# POE.net
KiCad netlist of a schematic drawn in Altium Designer
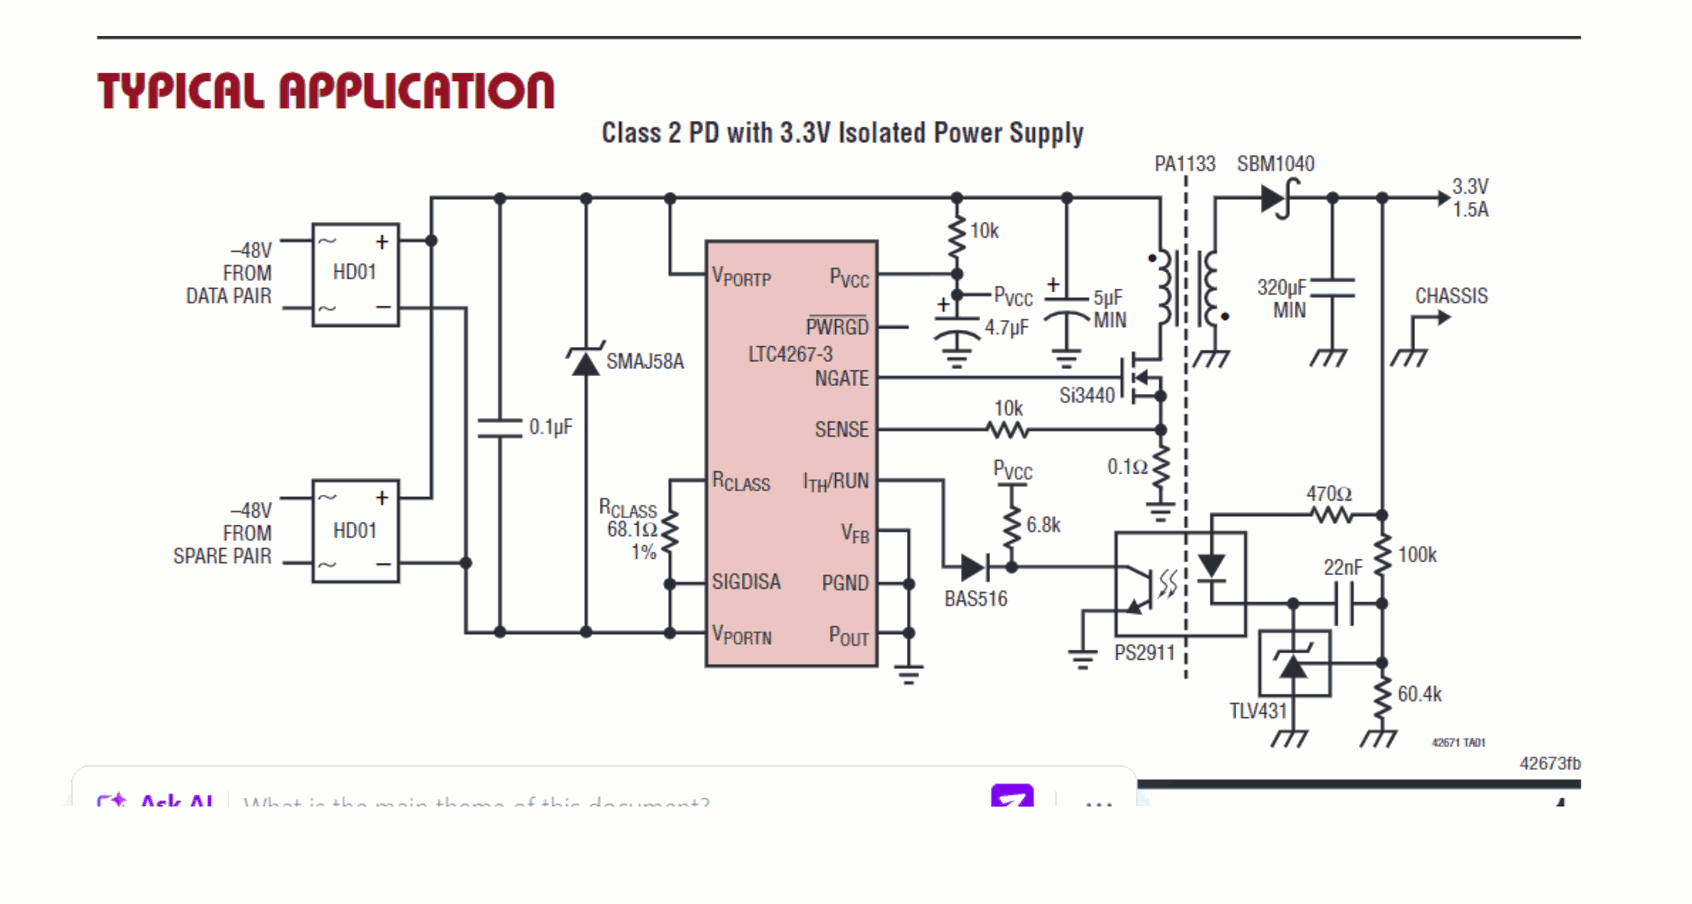
[diagram p0: POE.SchDoc, top left]
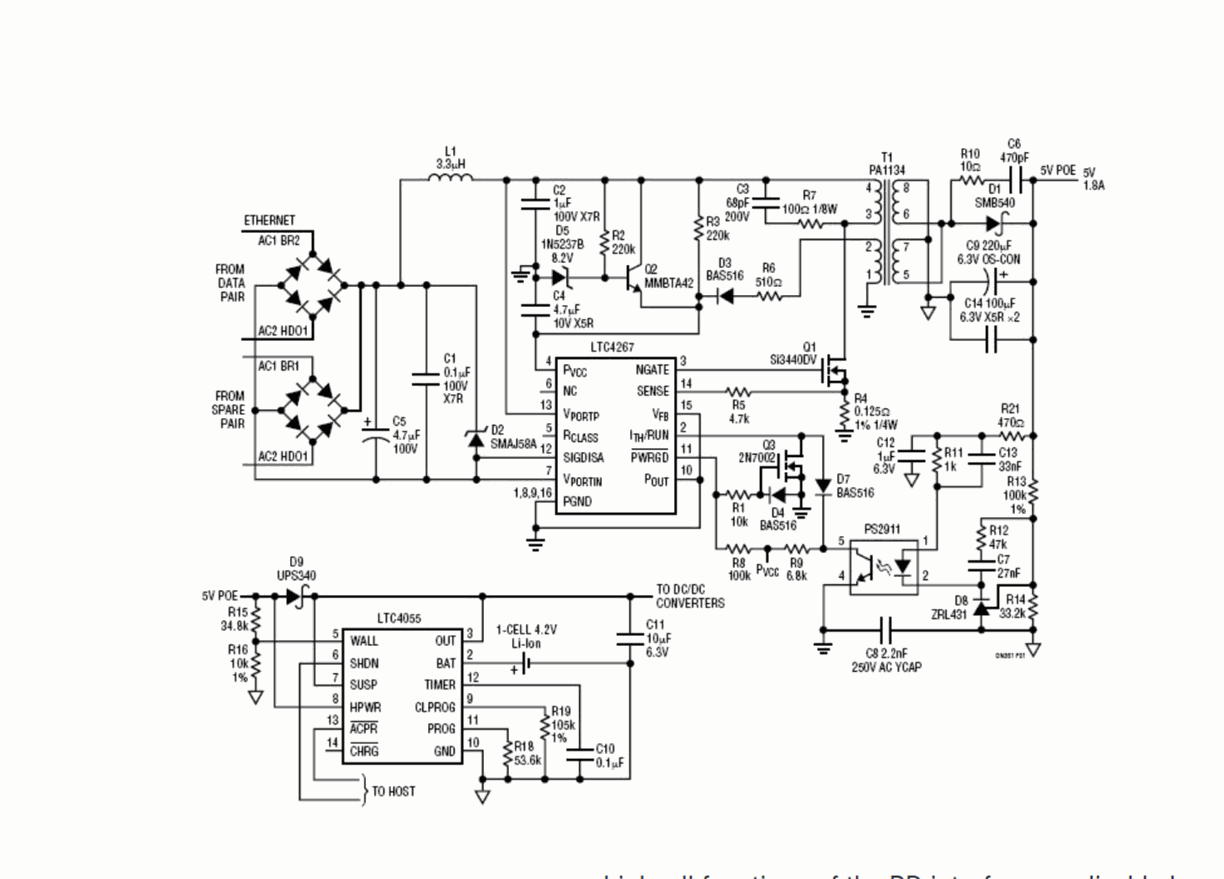
[diagram p1: POE.SchDoc, top right]
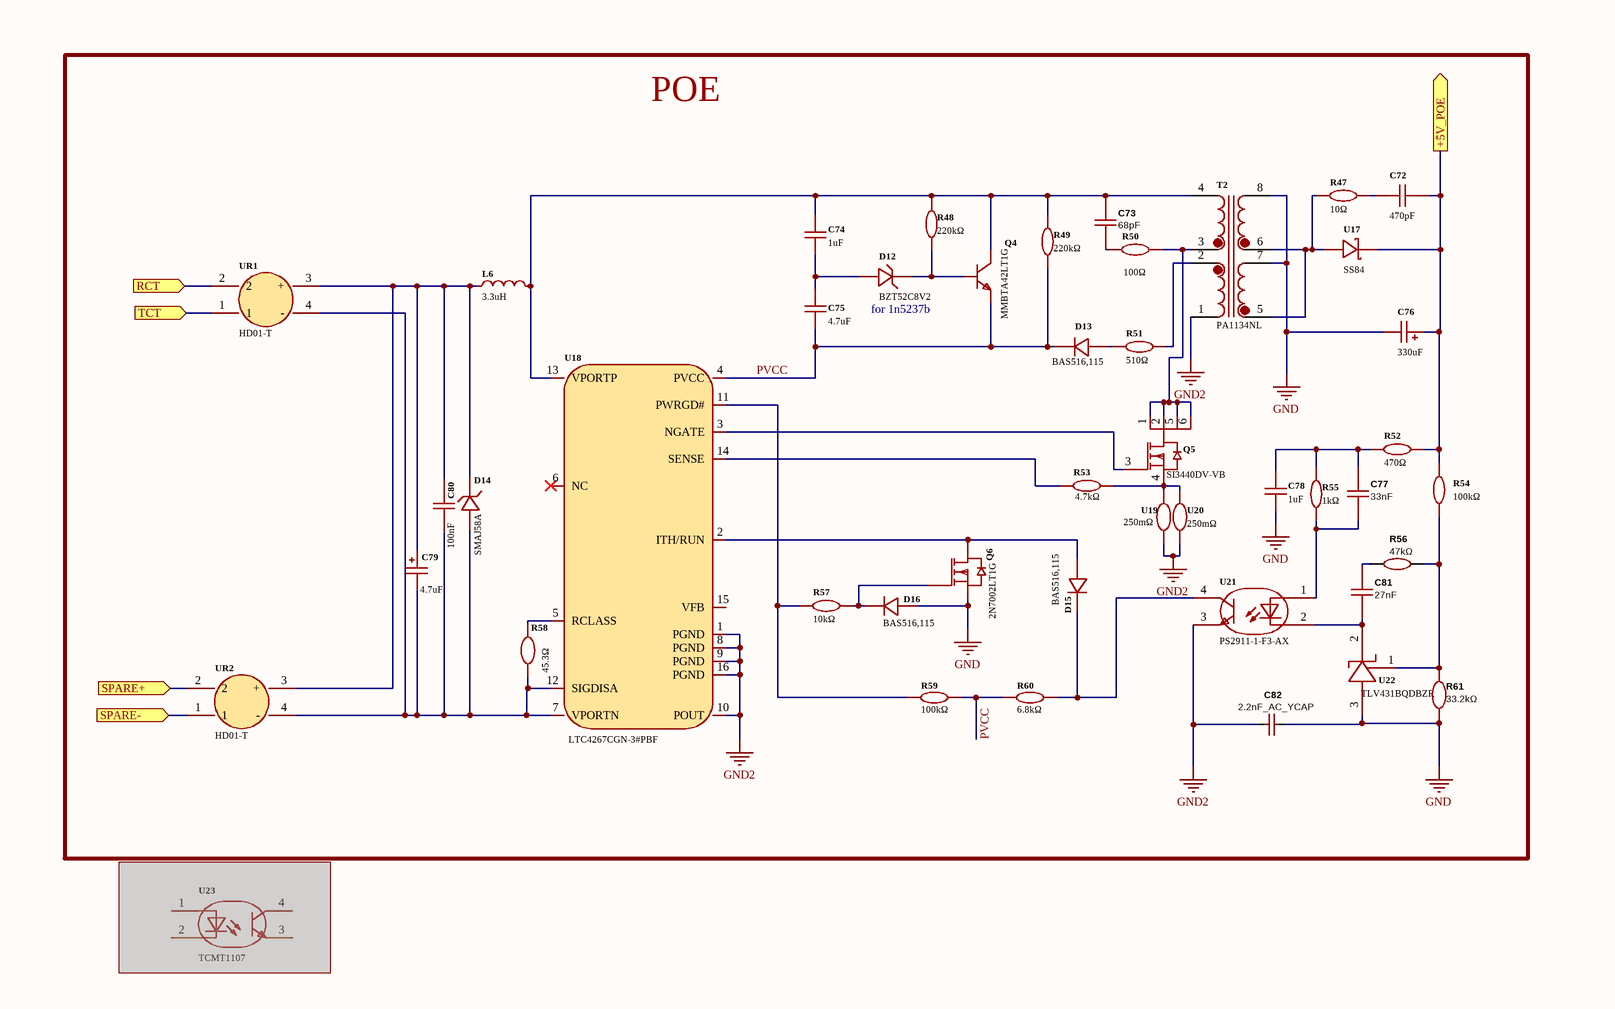
[diagram p2: POE.SchDoc, bottom left]
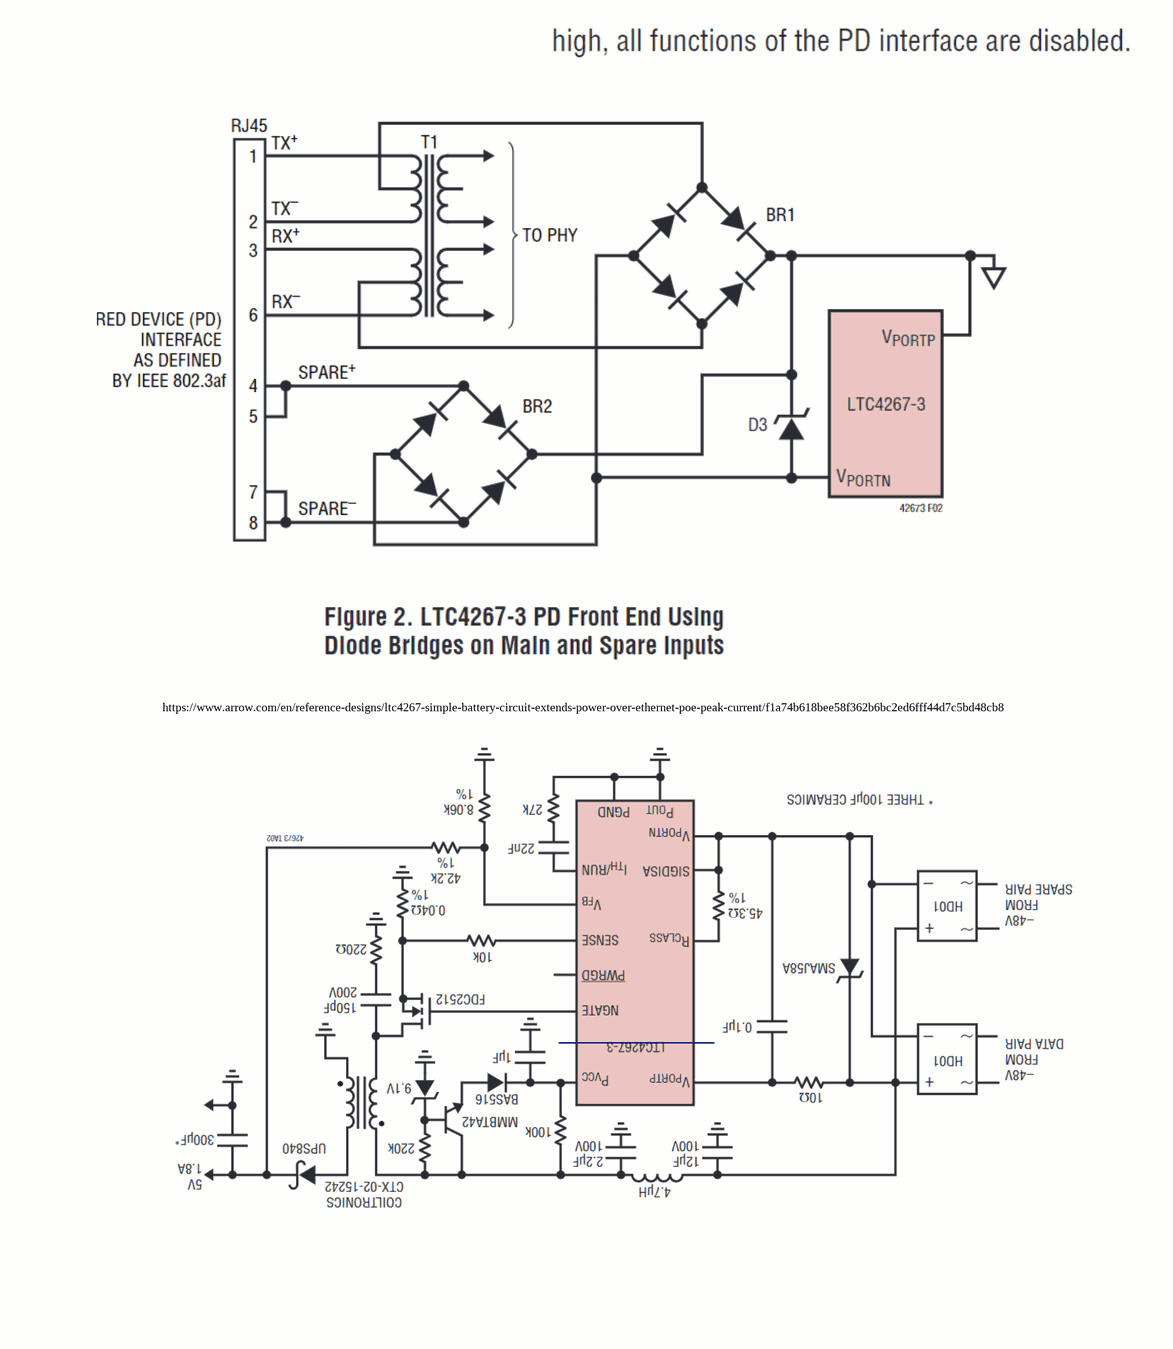
[diagram p3: POE.SchDoc, bottom right]

(export (version "E")
  (design (tool "Eeschema 10.0.6"))
  (components
    (comp (ref "C72")
      (value "470pF")
      (footprint "C_1206")
      (fields
        (field (name "MANUFACTURER") "YAGEO(国巨)")
        (field (name "MANUFACTURER PART") "CC1206JRNPOBBN471")
        (field (name "TOLERANCE") "±5%")
      )
      (libsource (lib "altium-import") (part "root_0_CC1206JRNPOBBN471_"))
    )
    (comp (ref "C73")
      (value "68pF")
      (footprint "C_1206")
      (fields
        (field (name "MANUFACTURER") "YAGEO(国巨)")
        (field (name "MANUFACTURER PART") "AC1206JRNPO0BN680")
        (field (name "CONTRIBUTOR") "lcsc")
      )
      (libsource (lib "altium-import") (part "root_1_68pF_"))
    )
    (comp (ref "C74")
      (value "1uF")
      (footprint "C_0805")
      (fields
        (field (name "MANUFACTURER PART") "CL21B105KBFNNNE")
        (field (name "MANUFACTURER") "SAMSUNG(三星)")
        (field (name "TOLERANCE") "±10%")
      )
      (libsource (lib "altium-import") (part "root_1_CL21B105KBFNNNE_"))
    )
    (comp (ref "C75")
      (value "4.7uF")
      (footprint "C_0805")
      (fields
        (field (name "MANUFACTURER") "SAMSUNG(三星)")
        (field (name "MANUFACTURER PART") "CL21A475KBQNNNE")
        (field (name "TOLERANCE") "±10%")
      )
      (libsource (lib "altium-import") (part "root_1_CL21A475KBQNNNE_"))
    )
    (comp (ref "C76")
      (value "330uF")
      (footprint "CASE-D_7343")
      (fields
        (field (name "MANUFACTURER") "Kyocera AVX")
        (field (name "MANUFACTURER PART") "TAJD337K010RNJ")
        (field (name "TOLERANCE") "±10%")
      )
      (libsource (lib "altium-import") (part "root_0_TAJD337K010RNJ_"))
    )
    (comp (ref "C77")
      (value "33nF")
      (footprint "C_0805")
      (fields
        (field (name "MANUFACTURER") "YAGEO(国巨)")
        (field (name "MANUFACTURER PART") "CC0805JRX7R9BB333")
        (field (name "CONTRIBUTOR") "LCSC")
      )
      (libsource (lib "altium-import") (part "root_1_33nF_"))
    )
    (comp (ref "C78")
      (value "1uF")
      (footprint "C_0805")
      (fields
        (field (name "MANUFACTURER PART") "CL21B105KBFNNNE")
        (field (name "MANUFACTURER") "SAMSUNG(三星)")
        (field (name "TOLERANCE") "±10%")
      )
      (libsource (lib "altium-import") (part "root_1_CL21B105KBFNNNE_"))
    )
    (comp (ref "C79")
      (value "4.7uF")
      (footprint "CAP-SMD_L6.0-W3.2-R-RD")
      (fields
        (field (name "MANUFACTURER") "Kyocera AVX")
        (field (name "MANUFACTURER PART") "TAJC475K035RNJ")
        (field (name "TOLERANCE") "±10%")
      )
      (libsource (lib "altium-import") (part "root_1_mirrored_TAJC475K035RNJ_"))
    )
    (comp (ref "C80")
      (value "100nF")
      (footprint "C_0603")
      (fields
        (field (name "MANUFACTURER") "YAGEO(国巨)")
        (field (name "MANUFACTURER PART") "CC0603KRX7R9BB104")
        (field (name "TOLERANCE") "±10%")
      )
      (libsource (lib "altium-import") (part "root_3_CC0603KRX7R9BB104_"))
    )
    (comp (ref "C81")
      (value "27nF")
      (footprint "C_0805")
      (fields
        (field (name "MANUFACTURER") "YAGEO(国巨)")
        (field (name "MANUFACTURER PART") "CC0805JRX7R9BB273")
        (field (name "CONTRIBUTOR") "LCSC")
      )
      (libsource (lib "altium-import") (part "root_1_27nF_"))
    )
    (comp (ref "C82")
      (value "2.2nF_AC_YCAP")
      (footprint "C_1206")
      (fields
        (field (name "MANUFACTURER") "FH(风华)")
        (field (name "MANUFACTURER PART") "1206B222K251NT")
        (field (name "CONTRIBUTOR") "LCSC")
      )
      (libsource (lib "altium-import") (part "root_0_2.2nF_"))
    )
    (comp (ref "D12")
      (value "BZT52C8V2")
      (footprint "SOD-123_L2.8-W1.8-LS3.7-RD")
      (fields (field (name "MANUFACTURER") "MDD(辰达半导体)"))
      (libsource (lib "altium-import") (part "root_2_BZT52C8V2_C173432_"))
    )
    (comp (ref "D13")
      (value "BAS516,115")
      (footprint "SOD-523F_L1.2-W0.8-LS1.7-RD")
      (fields (field (name "MANUFACTURER") "Nexperia(安世)"))
      (libsource (lib "altium-import") (part "root_0_BAS516,115_"))
    )
    (comp (ref "D14")
      (value "SMAJ58A")
      (footprint "SMA_L4.3-W2.6-LS5.2-RD")
      (fields (field (name "MANUFACTURER") "Littelfuse(美国力特)"))
      (libsource (lib "altium-import") (part "root_3_SMAJ58A_C151246_"))
    )
    (comp (ref "D15")
      (value "BAS516,115")
      (footprint "SOD-523F_L1.2-W0.8-LS1.7-RD")
      (fields (field (name "MANUFACTURER") "Nexperia(安世)"))
      (libsource (lib "altium-import") (part "root_1_BAS516,115_"))
    )
    (comp (ref "D16")
      (value "BAS516,115")
      (footprint "SOD-523F_L1.2-W0.8-LS1.7-RD")
      (fields (field (name "MANUFACTURER") "Nexperia(安世)"))
      (libsource (lib "altium-import") (part "root_0_BAS516,115_"))
    )
    (comp (ref "L6")
      (value "3.3uH")
      (footprint "IND-SMD_L5.4-W5.2_PSPMAA0503")
      (fields
        (field (name "MANUFACTURER") "PROD(谱罗德)")
        (field (name "MANUFACTURER PART") "PSPMAA0503-3R3M-ANP")
        (field (name "TOLERANCE") "±20%")
      )
      (libsource (lib "altium-import") (part "root_0_PSPMAA0503-3R3M-ANP_"))
    )
    (comp (ref "Q4")
      (value "MMBTA42LT1G")
      (footprint "SOT-23-3_L2.9-W1.6-P1.90-LS2.8-BR")
      (fields (field (name "MANUFACTURER") "onsemi(安森美)"))
      (libsource (lib "altium-import") (part "root_0_MMBTA42LT1G_"))
    )
    (comp (ref "Q5")
      (value "SI3440DV-VB")
      (footprint "SOT-23-6_L2.9-W1.6-P0.95-LS2.8-BR")
      (fields (field (name "MANUFACTURER") "VBsemi(微碧半导体)"))
      (libsource (lib "EsoCore_Edge_Board_V1-0.0.0") (part "SI3440DV-VB"))
    )
    (comp (ref "Q6")
      (value "2N7002LT1G")
      (footprint "SOT-23_L2.9-W1.3-P1.90-LS2.4-BR")
      (fields (field (name "MANUFACTURER") "onsemi(安森美)"))
      (libsource (lib "altium-import") (part "root_0_2N7002LT1G_"))
    )
    (comp (ref "R47")
      (value "10Ω")
      (footprint "R_1206")
      (fields
        (field (name "MANUFACTURER") "YAGEO(国巨)")
        (field (name "MANUFACTURER PART") "RC1206FR-0710RL")
        (field (name "TOLERANCE") "±1%")
      )
      (libsource (lib "altium-import") (part "root_0_RC1206FR-0710RL_"))
    )
    (comp (ref "R48")
      (value "220kΩ")
      (footprint "R_0805")
      (fields
        (field (name "MANUFACTURER") "YAGEO(国巨)")
        (field (name "MANUFACTURER PART") "RC0805JR-07220KL")
        (field (name "TOLERANCE") "±5%")
      )
      (libsource (lib "altium-import") (part "root_1_RC0805JR-07220KL_"))
    )
    (comp (ref "R49")
      (value "220kΩ")
      (footprint "R_0805")
      (fields
        (field (name "MANUFACTURER") "YAGEO(国巨)")
        (field (name "MANUFACTURER PART") "RC0805JR-07220KL")
        (field (name "TOLERANCE") "±5%")
      )
      (libsource (lib "altium-import") (part "root_1_RC0805JR-07220KL_"))
    )
    (comp (ref "R50")
      (value "100Ω")
      (footprint "R_0805")
      (fields
        (field (name "MANUFACTURER") "YAGEO(国巨)")
        (field (name "MANUFACTURER PART") "RC0805FR-07100RL")
        (field (name "TOLERANCE") "±1%")
      )
      (libsource (lib "altium-import") (part "root_0_RC0805FR-07100RL_"))
    )
    (comp (ref "R51")
      (value "510Ω")
      (footprint "R_0805")
      (fields
        (field (name "MANUFACTURER") "YAGEO(国巨)")
        (field (name "MANUFACTURER PART") "RC0805FR-07510RL")
        (field (name "TOLERANCE") "±1%")
      )
      (libsource (lib "altium-import") (part "root_0_RC0805FR-07510RL_"))
    )
    (comp (ref "R52")
      (value "470Ω")
      (footprint "R_1206")
      (fields
        (field (name "MANUFACTURER") "UNI-ROYAL(厚声)")
        (field (name "MANUFACTURER PART") "1206W4F4700T5E")
        (field (name "TOLERANCE") "±1%")
      )
      (libsource (lib "altium-import") (part "root_0_1206W4F4700T5E_"))
    )
    (comp (ref "R53")
      (value "4.7kΩ")
      (footprint "R_0805")
      (fields
        (field (name "MANUFACTURER") "YAGEO(国巨)")
        (field (name "MANUFACTURER PART") "RC0805JR-074K7L")
        (field (name "TOLERANCE") "±5%")
      )
      (libsource (lib "altium-import") (part "root_0_RC0805JR-074K7L_"))
    )
    (comp (ref "R54")
      (value "100kΩ")
      (footprint "R_0805")
      (fields
        (field (name "MANUFACTURER") "YAGEO(国巨)")
        (field (name "MANUFACTURER PART") "RC0805FR-07100KL")
        (field (name "TOLERANCE") "±1%")
      )
      (libsource (lib "altium-import") (part "root_1_RC0805FR-07100KL_"))
    )
    (comp (ref "R55")
      (value "1kΩ")
      (footprint "R_0805")
      (fields
        (field (name "MANUFACTURER") "YAGEO(国巨)")
        (field (name "MANUFACTURER PART") "RC0805FR-071KL")
        (field (name "TOLERANCE") "±1%")
      )
      (libsource (lib "altium-import") (part "root_1_RC0805FR-071KL_"))
    )
    (comp (ref "R56")
      (value "47kΩ")
      (footprint "R_0805")
      (fields (field (name "MANUFACTURER") "YAGEO(国巨)") (field (name "MANUFACTURER PART") "RC0805FR-0747KL"))
      (libsource (lib "altium-import") (part "root_0_47kΩ_"))
    )
    (comp (ref "R57")
      (value "10kΩ")
      (footprint "R_0805")
      (fields
        (field (name "MANUFACTURER") "YAGEO(国巨)")
        (field (name "MANUFACTURER PART") "RC0805FR-0710KL")
        (field (name "TOLERANCE") "±1%")
      )
      (libsource (lib "altium-import") (part "root_0_RC0805FR-0710KL_"))
    )
    (comp (ref "R58")
      (value "45.3Ω")
      (footprint "R_0805")
      (fields
        (field (name "MANUFACTURER") "YAGEO(国巨)")
        (field (name "MANUFACTURER PART") "RT0805BRD0745R3L")
        (field (name "TOLERANCE") "±0.1%")
      )
      (libsource (lib "altium-import") (part "root_1_mirrored_RT0805BRD0745R3L_"))
    )
    (comp (ref "R59")
      (value "100kΩ")
      (footprint "R_0805")
      (fields
        (field (name "MANUFACTURER") "YAGEO(国巨)")
        (field (name "MANUFACTURER PART") "RC0805FR-07100KL")
        (field (name "TOLERANCE") "±1%")
      )
      (libsource (lib "altium-import") (part "root_2_RC0805FR-07100KL_"))
    )
    (comp (ref "R60")
      (value "6.8kΩ")
      (footprint "R_0603")
      (fields
        (field (name "MANUFACTURER") "YAGEO(国巨)")
        (field (name "MANUFACTURER PART") "RC0603FR-076K8L")
        (field (name "TOLERANCE") "±1%")
      )
      (libsource (lib "altium-import") (part "root_2_RC0603FR-076K8L_"))
    )
    (comp (ref "R61")
      (value "33.2kΩ")
      (footprint "R_0805")
      (fields
        (field (name "MANUFACTURER") "YAGEO(国巨)")
        (field (name "MANUFACTURER PART") "RC0805FR-0733K2L")
        (field (name "CONTRIBUTOR") "LCSC")
      )
      (libsource (lib "altium-import") (part "root_1_33.2kΩ_"))
    )
    (comp (ref "T2")
      (value "PA1134NL")
      (footprint "XFMR_PA1134NL")
      (description "253ÂµH Isolation and Data Interface (Encapsulated) Pulse Transformer 1:0.125:0.208 Surface Mount")
      (fields (field (name "MF") "Pulse"))
      (libsource (lib "EsoCore_Edge_Board_V1-0.0.0") (part "PA1134NL"))
    )
    (comp (ref "U17")
      (value "SS84")
      (footprint "SMC_L6.9-W5.9-LS7.9-RD")
      (fields (field (name "MANUFACTURER") "GOODWORK(固得沃克)"))
      (libsource (lib "altium-import") (part "root_2_SS84_"))
    )
    (comp (ref "U18")
      (value "LTC4267CGN-3#PBF")
      (footprint "SSOP-16_L4.9-W3.9-P0.64-LS6.0-BL")
      (fields (field (name "MANUFACTURER") "ADI(亚德诺)"))
      (libsource (lib "EsoCore_Edge_Board_V1-0.0.0") (part "LTC4267CGN-3#PBF"))
    )
    (comp (ref "U19")
      (value "250mΩ")
      (footprint "R2512")
      (fields
        (field (name "MANUFACTURER") "Milliohm(毫欧)")
        (field (name "MANUFACTURER PART") "HoJLR2512-3W-250mR-1%")
        (field (name "TOLERANCE") "±1%")
      )
      (libsource (lib "altium-import") (part "root_1_HoJLR2512-3W-250mR-1%_"))
    )
    (comp (ref "U20")
      (value "250mΩ")
      (footprint "R2512")
      (fields
        (field (name "MANUFACTURER") "Milliohm(毫欧)")
        (field (name "MANUFACTURER PART") "HoJLR2512-3W-250mR-1%")
        (field (name "TOLERANCE") "±1%")
      )
      (libsource (lib "altium-import") (part "root_1_HoJLR2512-3W-250mR-1%_"))
    )
    (comp (ref "U21")
      (value "PS2911-1-F3-AX")
      (footprint "OPTO-SMD_PS2911-1-F3-AX")
      (fields (field (name "MANUFACTURER") "RENESAS(瑞萨)/IDT"))
      (libsource (lib "EsoCore_Edge_Board_V1-0.0.0") (part "PS2911-1-F3-AX_C5334506"))
    )
    (comp (ref "U22")
      (value "TLV431BQDBZR")
      (footprint "SOT-23-3_L2.9-W1.3-P0.95-LS2.4-BR")
      (fields (field (name "MANUFACTURER") "TI(德州仪器)") (field (name "TOLERANCE") "±0.5%"))
      (libsource (lib "EsoCore_Edge_Board_V1-0.0.0") (part "TLV431BQDBZR"))
    )
    (comp (ref "U23")
      (value "TCMT1107")
      (footprint "SOP-4_L4.4-W2.8-P1.27-LS7.0-TL")
      (fields (field (name "MANUFACTURER") "VISHAY(威世)"))
      (libsource (lib "altium-import") (part "root_0_TCMT1107_"))
    )
    (comp (ref "UR1")
      (value "HD01-T")
      (footprint "MBS_L4.7-W4.0-P2.50-LS7.0-TL")
      (fields (field (name "MANUFACTURER") "DIODES(美台)"))
      (libsource (lib "EsoCore_Edge_Board_V1-0.0.0") (part "HD01-T"))
    )
    (comp (ref "UR2")
      (value "HD01-T")
      (footprint "MBS_L4.7-W4.0-P2.50-LS7.0-TL")
      (fields (field (name "MANUFACTURER") "DIODES(美台)"))
      (libsource (lib "EsoCore_Edge_Board_V1-0.0.0") (part "HD01-T"))
    )
  )
  (nets
    (net (code "1") (name "/+5V_POE") (class "Default")
      (node (ref "C72") (pin "2") (pinfunction "2_2") (pintype "passive"))
      (node (ref "C76") (pin "1") (pinfunction "1_1") (pintype "passive"))
      (node (ref "R52") (pin "2") (pinfunction "2_2") (pintype "passive"))
      (node (ref "R54") (pin "2") (pinfunction "2_2") (pintype "passive"))
      (node (ref "U17") (pin "1") (pinfunction "K_1") (pintype "passive"))
    )
    (net (code "2") (name "/PVCC") (class "Default")
      (node (ref "C75") (pin "1") (pinfunction "1_1") (pintype "passive"))
      (node (ref "D13") (pin "1") (pinfunction "C_1") (pintype "passive"))
      (node (ref "Q4") (pin "2") (pinfunction "2_2") (pintype "passive"))
      (node (ref "R49") (pin "1") (pinfunction "1_1") (pintype "passive"))
      (node (ref "R59") (pin "1") (pinfunction "1_1") (pintype "passive"))
      (node (ref "R60") (pin "2") (pinfunction "2_2") (pintype "passive"))
      (node (ref "U18") (pin "4") (pinfunction "PVCC_4") (pintype "passive"))
    )
    (net (code "3") (name "/RCT") (class "Default")
      (node (ref "UR1") (pin "2") (pinfunction "2_2") (pintype "passive"))
    )
    (net (code "4") (name "/SPARE+") (class "Default")
      (node (ref "UR2") (pin "2") (pinfunction "2_2") (pintype "passive"))
    )
    (net (code "5") (name "/SPARE-") (class "Default")
      (node (ref "UR2") (pin "1") (pinfunction "1_1") (pintype "passive"))
    )
    (net (code "6") (name "/TCT") (class "Default")
      (node (ref "UR1") (pin "1") (pinfunction "1_1") (pintype "passive"))
    )
    (net (code "7") (name "GND") (class "Default")
      (node (ref "C76") (pin "2") (pinfunction "2_2") (pintype "passive"))
      (node (ref "C78") (pin "1") (pinfunction "1_1") (pintype "passive"))
      (node (ref "C82") (pin "2") (pinfunction "2_2") (pintype "passive"))
      (node (ref "D16") (pin "2") (pinfunction "A_2") (pintype "passive"))
      (node (ref "Q6") (pin "2") (pinfunction "S_2") (pintype "passive"))
      (node (ref "R61") (pin "1") (pinfunction "1_1") (pintype "passive"))
      (node (ref "T2") (pin "7") (pinfunction "7_7") (pintype "passive"))
      (node (ref "T2") (pin "8") (pinfunction "8_8") (pintype "passive"))
      (node (ref "U22") (pin "3") (pinfunction "ANODE_3") (pintype "passive"))
    )
    (net (code "8") (name "GND2") (class "Default")
      (node (ref "C82") (pin "1") (pinfunction "1_1") (pintype "passive"))
      (node (ref "T2") (pin "1") (pinfunction "1_1") (pintype "passive"))
      (node (ref "U18") (pin "1") (pinfunction "PGND_1") (pintype "passive"))
      (node (ref "U18") (pin "10") (pinfunction "POUT_10") (pintype "passive"))
      (node (ref "U18") (pin "16") (pinfunction "PGND_16") (pintype "passive"))
      (node (ref "U18") (pin "8") (pinfunction "PGND_8") (pintype "passive"))
      (node (ref "U18") (pin "9") (pinfunction "PGND_9") (pintype "passive"))
      (node (ref "U19") (pin "1") (pinfunction "1_1") (pintype "passive"))
      (node (ref "U20") (pin "1") (pinfunction "1_1") (pintype "passive"))
      (node (ref "U21") (pin "3") (pinfunction "Emitter_3") (pintype "passive"))
    )
    (net (code "9") (name "Net-(C72-Pad1)") (class "Default")
      (node (ref "C72") (pin "1") (pinfunction "1_1") (pintype "passive"))
      (node (ref "R47") (pin "2") (pinfunction "2_2") (pintype "passive"))
    )
    (net (code "10") (name "Net-(C73-Pad1)") (class "Default")
      (node (ref "C73") (pin "1") (pinfunction "1_1") (pintype "passive"))
      (node (ref "R50") (pin "1") (pinfunction "1_1") (pintype "passive"))
    )
    (net (code "11") (name "Net-(C74-Pad1)") (class "Default")
      (node (ref "C74") (pin "1") (pinfunction "1_1") (pintype "passive"))
      (node (ref "C75") (pin "2") (pinfunction "2_2") (pintype "passive"))
      (node (ref "D12") (pin "2") (pinfunction "2_2") (pintype "passive"))
    )
    (net (code "12") (name "Net-(C77-Pad2)") (class "Default")
      (node (ref "C77") (pin "2") (pinfunction "2_2") (pintype "passive"))
      (node (ref "C78") (pin "2") (pinfunction "2_2") (pintype "passive"))
      (node (ref "R52") (pin "1") (pinfunction "1_1") (pintype "passive"))
      (node (ref "R55") (pin "2") (pinfunction "2_2") (pintype "passive"))
    )
    (net (code "13") (name "Net-(C81-Pad2)") (class "Default")
      (node (ref "C81") (pin "2") (pinfunction "2_2") (pintype "passive"))
      (node (ref "R56") (pin "1") (pinfunction "1_1") (pintype "passive"))
    )
    (net (code "14") (name "Net-(D12-Pad1)") (class "Default")
      (node (ref "D12") (pin "1") (pinfunction "1_1") (pintype "passive"))
      (node (ref "Q4") (pin "1") (pinfunction "1_1") (pintype "passive"))
      (node (ref "R48") (pin "1") (pinfunction "1_1") (pintype "passive"))
    )
    (net (code "15") (name "Net-(D13-A)") (class "Default")
      (node (ref "D13") (pin "2") (pinfunction "A_2") (pintype "passive"))
      (node (ref "R51") (pin "1") (pinfunction "1_1") (pintype "passive"))
    )
    (net (code "16") (name "Net-(D14-A)") (class "Default")
      (node (ref "C79") (pin "2") (pinfunction "2_2") (pintype "passive"))
      (node (ref "C80") (pin "2") (pinfunction "2_2") (pintype "passive"))
      (node (ref "D14") (pin "2") (pinfunction "A_2") (pintype "passive"))
      (node (ref "R58") (pin "1") (pinfunction "1_1") (pintype "passive"))
      (node (ref "U18") (pin "12") (pinfunction "SIGDISA_12") (pintype "passive"))
      (node (ref "U18") (pin "7") (pinfunction "VPORTN_7") (pintype "passive"))
      (node (ref "UR1") (pin "4") (pinfunction "-_4") (pintype "passive"))
      (node (ref "UR2") (pin "4") (pinfunction "-_4") (pintype "passive"))
    )
    (net (code "17") (name "Net-(D14-C)") (class "Default")
      (node (ref "C79") (pin "1") (pinfunction "1_1") (pintype "passive"))
      (node (ref "C80") (pin "1") (pinfunction "1_1") (pintype "passive"))
      (node (ref "D14") (pin "1") (pinfunction "C_1") (pintype "passive"))
      (node (ref "L6") (pin "1") (pinfunction "1_1") (pintype "passive"))
      (node (ref "UR1") (pin "3") (pinfunction "+_3") (pintype "passive"))
      (node (ref "UR2") (pin "3") (pinfunction "+_3") (pintype "passive"))
    )
    (net (code "18") (name "Net-(D15-A)") (class "Default")
      (node (ref "D15") (pin "2") (pinfunction "A_2") (pintype "passive"))
      (node (ref "Q6") (pin "3") (pinfunction "D_3") (pintype "passive"))
      (node (ref "U18") (pin "2") (pinfunction "ITH/RUN_2") (pintype "passive"))
    )
    (net (code "19") (name "Net-(D15-C)") (class "Default")
      (node (ref "D15") (pin "1") (pinfunction "C_1") (pintype "passive"))
      (node (ref "R60") (pin "1") (pinfunction "1_1") (pintype "passive"))
      (node (ref "U21") (pin "4") (pinfunction "Collector_4") (pintype "passive"))
    )
    (net (code "20") (name "Net-(D16-C)") (class "Default")
      (node (ref "D16") (pin "1") (pinfunction "C_1") (pintype "passive"))
      (node (ref "Q6") (pin "1") (pinfunction "G_1") (pintype "passive"))
      (node (ref "R57") (pin "2") (pinfunction "2_2") (pintype "passive"))
    )
    (net (code "21") (name "Net-(Q5-D-Pad1)") (class "Default")
      (node (ref "Q5") (pin "1") (pinfunction "D_1") (pintype "passive"))
      (node (ref "Q5") (pin "2") (pinfunction "D_2") (pintype "passive"))
      (node (ref "Q5") (pin "5") (pinfunction "D_5") (pintype "passive"))
      (node (ref "Q5") (pin "6") (pinfunction "D_6") (pintype "passive"))
      (node (ref "R50") (pin "2") (pinfunction "2_2") (pintype "passive"))
      (node (ref "T2") (pin "3") (pinfunction "3_3") (pintype "passive"))
    )
    (net (code "22") (name "Net-(Q5-G)") (class "Default")
      (node (ref "Q5") (pin "3") (pinfunction "G_3") (pintype "passive"))
      (node (ref "U18") (pin "3") (pinfunction "NGATE_3") (pintype "passive"))
    )
    (net (code "23") (name "Net-(Q5-S)") (class "Default")
      (node (ref "Q5") (pin "4") (pinfunction "S_4") (pintype "passive"))
      (node (ref "R53") (pin "2") (pinfunction "2_2") (pintype "passive"))
      (node (ref "U19") (pin "2") (pinfunction "2_2") (pintype "passive"))
      (node (ref "U20") (pin "2") (pinfunction "2_2") (pintype "passive"))
    )
    (net (code "24") (name "Net-(R51-Pad2)") (class "Default")
      (node (ref "R51") (pin "2") (pinfunction "2_2") (pintype "passive"))
      (node (ref "T2") (pin "2") (pinfunction "2_2") (pintype "passive"))
    )
    (net (code "25") (name "Net-(U17-A)") (class "Default")
      (node (ref "R47") (pin "1") (pinfunction "1_1") (pintype "passive"))
      (node (ref "T2") (pin "5") (pinfunction "5_5") (pintype "passive"))
      (node (ref "T2") (pin "6") (pinfunction "6_6") (pintype "passive"))
      (node (ref "U17") (pin "2") (pinfunction "A_2") (pintype "passive"))
    )
    (net (code "26") (name "Net-(U18-PWRGD#)") (class "Default")
      (node (ref "R57") (pin "1") (pinfunction "1_1") (pintype "passive"))
      (node (ref "R59") (pin "2") (pinfunction "2_2") (pintype "passive"))
      (node (ref "U18") (pin "11") (pinfunction "PWRGD#_11") (pintype "passive"))
    )
    (net (code "27") (name "Net-(U18-RCLASS)") (class "Default")
      (node (ref "R58") (pin "2") (pinfunction "2_2") (pintype "passive"))
      (node (ref "U18") (pin "5") (pinfunction "RCLASS_5") (pintype "passive"))
    )
    (net (code "28") (name "Net-(U18-SENSE)") (class "Default")
      (node (ref "R53") (pin "1") (pinfunction "1_1") (pintype "passive"))
      (node (ref "U18") (pin "14") (pinfunction "SENSE_14") (pintype "passive"))
    )
    (net (code "29") (name "Net-(U18-VPORTP)") (class "Default")
      (node (ref "C73") (pin "2") (pinfunction "2_2") (pintype "passive"))
      (node (ref "C74") (pin "2") (pinfunction "2_2") (pintype "passive"))
      (node (ref "L6") (pin "2") (pinfunction "2_2") (pintype "passive"))
      (node (ref "Q4") (pin "3") (pinfunction "3_3") (pintype "passive"))
      (node (ref "R48") (pin "2") (pinfunction "2_2") (pintype "passive"))
      (node (ref "R49") (pin "2") (pinfunction "2_2") (pintype "passive"))
      (node (ref "T2") (pin "4") (pinfunction "4_4") (pintype "passive"))
      (node (ref "U18") (pin "13") (pinfunction "VPORTP_13") (pintype "passive"))
    )
    (net (code "30") (name "Net-(U21-Anode)") (class "Default")
      (node (ref "C77") (pin "1") (pinfunction "1_1") (pintype "passive"))
      (node (ref "R55") (pin "1") (pinfunction "1_1") (pintype "passive"))
      (node (ref "U21") (pin "1") (pinfunction "Anode_1") (pintype "passive"))
    )
    (net (code "31") (name "Net-(U21-Cathode)") (class "Default")
      (node (ref "C81") (pin "1") (pinfunction "1_1") (pintype "passive"))
      (node (ref "U21") (pin "2") (pinfunction "Cathode_2") (pintype "passive"))
      (node (ref "U22") (pin "2") (pinfunction "CATHODE_2") (pintype "passive"))
    )
    (net (code "32") (name "Net-(U22-REF)") (class "Default")
      (node (ref "R54") (pin "1") (pinfunction "1_1") (pintype "passive"))
      (node (ref "R56") (pin "2") (pinfunction "2_2") (pintype "passive"))
      (node (ref "R61") (pin "2") (pinfunction "2_2") (pintype "passive"))
      (node (ref "U22") (pin "1") (pinfunction "REF_1") (pintype "passive"))
    )
    (net (code "33") (name "unconnected-(U18-NC-Pad6)") (class "Default")
      (node (ref "U18") (pin "6") (pinfunction "NC_6") (pintype "passive+no_connect"))
    )
    (net (code "34") (name "unconnected-(U18-VFB-Pad15)") (class "Default")
      (node (ref "U18") (pin "15") (pinfunction "VFB_15") (pintype "passive"))
    )
    (net (code "35") (name "unconnected-(U23-AN-Pad1)") (class "Default")
      (node (ref "U23") (pin "1") (pinfunction "AN_1") (pintype "passive"))
    )
    (net (code "36") (name "unconnected-(U23-CAT-Pad2)") (class "Default")
      (node (ref "U23") (pin "2") (pinfunction "CAT_2") (pintype "passive"))
    )
    (net (code "37") (name "unconnected-(U23-COL-Pad4)") (class "Default")
      (node (ref "U23") (pin "4") (pinfunction "COL_4") (pintype "passive"))
    )
    (net (code "38") (name "unconnected-(U23-EM-Pad3)") (class "Default")
      (node (ref "U23") (pin "3") (pinfunction "EM_3") (pintype "passive"))
    )
  )
)
